# Power.net
KiCad netlist of a schematic drawn in Altium Designer
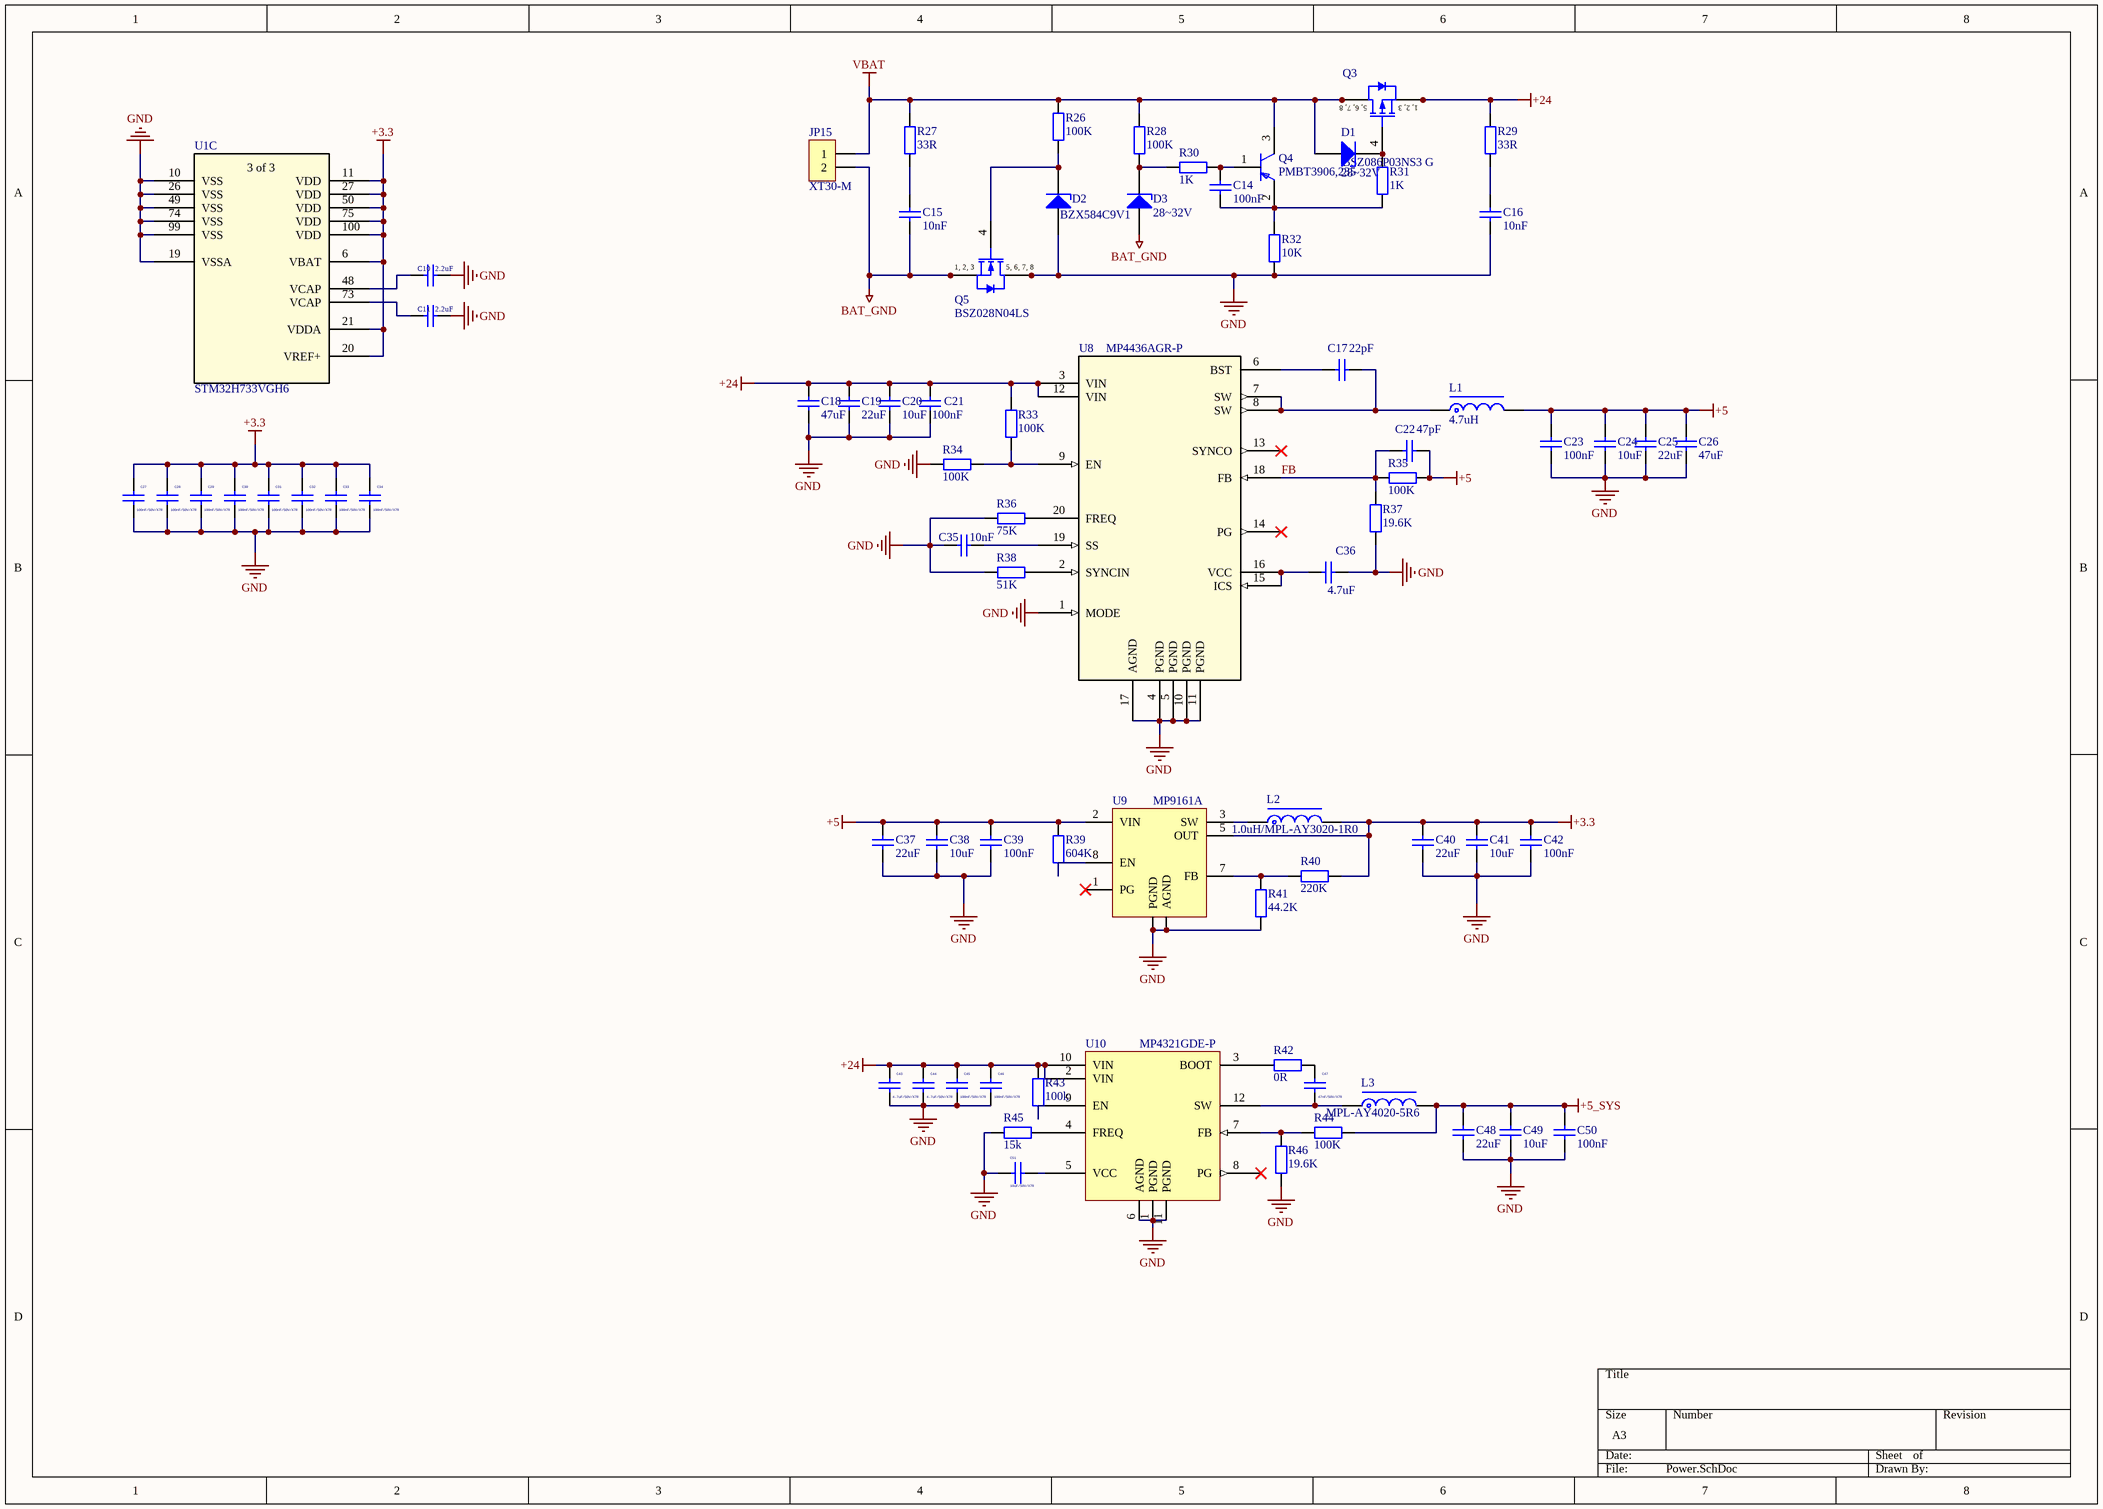
[diagram p0: Power.SchDoc]

(export (version "E")
  (design (tool "Eeschema 10.0.6"))
  (components
    (comp (ref "C10")
      (value "2.2uF")
      (footprint "C0402_L")
      (description "贴片电容/MLCC电容")
      (libsource (lib "0.1 - 电阻-电容-电感-保险丝-晶振-晶体-磁珠-电位器-法拉电容-馈通电容") (part "C"))
    )
    (comp (ref "C11")
      (value "2.2uF")
      (footprint "C0402_L")
      (description "贴片电容/MLCC电容")
      (libsource (lib "0.1 - 电阻-电容-电感-保险丝-晶振-晶体-磁珠-电位器-法拉电容-馈通电容") (part "C"))
    )
    (comp (ref "C14")
      (value "100nF")
      (footprint "C0402_M")
      (description "贴片电容/MLCC电容")
      (libsource (lib "海南大学MECHA战队") (part "C-EDLC"))
    )
    (comp (ref "C15")
      (value "10nF")
      (footprint "C0402_M")
      (description "贴片电容/MLCC电容")
      (libsource (lib "海南大学MECHA战队") (part "C-EDLC"))
    )
    (comp (ref "C16")
      (value "10nF")
      (footprint "C0402_M")
      (description "贴片电容/MLCC电容")
      (libsource (lib "海南大学MECHA战队") (part "C-EDLC"))
    )
    (comp (ref "C17")
      (value "22pF")
      (footprint "C0402_M")
      (description "贴片电容/MLCC电容")
      (libsource (lib "海南大学MECHA战队") (part "C-EDLC"))
    )
    (comp (ref "C18")
      (value "47uF")
      (footprint "C1206_L")
      (description "贴片电容/MLCC电容")
      (libsource (lib "0.1 - 电阻-电容-电感-保险丝-晶振-晶体-磁珠-电位器-法拉电容-馈通电容") (part "C"))
    )
    (comp (ref "C19")
      (value "22uF")
      (footprint "C0805_L")
      (description "贴片电容/MLCC电容")
      (libsource (lib "0.1 - 电阻-电容-电感-保险丝-晶振-晶体-磁珠-电位器-法拉电容-馈通电容") (part "C"))
    )
    (comp (ref "C20")
      (value "10uF")
      (footprint "C0603_L")
      (description "贴片电容/MLCC电容")
      (libsource (lib "0.1 - 电阻-电容-电感-保险丝-晶振-晶体-磁珠-电位器-法拉电容-馈通电容") (part "C"))
    )
    (comp (ref "C21")
      (value "100nF")
      (footprint "C0603_L")
      (description "贴片电容/MLCC电容")
      (libsource (lib "0.1 - 电阻-电容-电感-保险丝-晶振-晶体-磁珠-电位器-法拉电容-馈通电容") (part "C"))
    )
    (comp (ref "C22")
      (value "47pF")
      (footprint "C0402_M")
      (description "贴片电容/MLCC电容")
      (libsource (lib "海南大学MECHA战队") (part "C-EDLC"))
    )
    (comp (ref "C23")
      (value "100nF")
      (footprint "C0603_L")
      (description "贴片电容/MLCC电容")
      (libsource (lib "0.1 - 电阻-电容-电感-保险丝-晶振-晶体-磁珠-电位器-法拉电容-馈通电容") (part "C"))
    )
    (comp (ref "C24")
      (value "10uF")
      (footprint "C0603_L")
      (description "贴片电容/MLCC电容")
      (libsource (lib "0.1 - 电阻-电容-电感-保险丝-晶振-晶体-磁珠-电位器-法拉电容-馈通电容") (part "C"))
    )
    (comp (ref "C25")
      (value "22uF")
      (footprint "C0805_L")
      (description "贴片电容/MLCC电容")
      (libsource (lib "0.1 - 电阻-电容-电感-保险丝-晶振-晶体-磁珠-电位器-法拉电容-馈通电容") (part "C"))
    )
    (comp (ref "C26")
      (value "47uF")
      (footprint "C1206_L")
      (description "贴片电容/MLCC电容")
      (libsource (lib "0.1 - 电阻-电容-电感-保险丝-晶振-晶体-磁珠-电位器-法拉电容-馈通电容") (part "C"))
    )
    (comp (ref "C27")
      (value "100nF/50V/X7R")
      (footprint "C0402_L")
      (description "贴片电容/MLCC电容")
      (libsource (lib "0.1 - 电阻-电容-电感-保险丝-晶振-晶体-磁珠-电位器-法拉电容-馈通电容") (part "C"))
    )
    (comp (ref "C28")
      (value "100nF/50V/X7R")
      (footprint "C0402_L")
      (description "贴片电容/MLCC电容")
      (libsource (lib "0.1 - 电阻-电容-电感-保险丝-晶振-晶体-磁珠-电位器-法拉电容-馈通电容") (part "C"))
    )
    (comp (ref "C29")
      (value "100nF/50V/X7R")
      (footprint "C0402_L")
      (description "贴片电容/MLCC电容")
      (libsource (lib "0.1 - 电阻-电容-电感-保险丝-晶振-晶体-磁珠-电位器-法拉电容-馈通电容") (part "C"))
    )
    (comp (ref "C30")
      (value "100nF/50V/X7R")
      (footprint "C0402_L")
      (description "贴片电容/MLCC电容")
      (libsource (lib "0.1 - 电阻-电容-电感-保险丝-晶振-晶体-磁珠-电位器-法拉电容-馈通电容") (part "C"))
    )
    (comp (ref "C31")
      (value "100nF/50V/X7R")
      (footprint "C0402_L")
      (description "贴片电容/MLCC电容")
      (libsource (lib "0.1 - 电阻-电容-电感-保险丝-晶振-晶体-磁珠-电位器-法拉电容-馈通电容") (part "C"))
    )
    (comp (ref "C32")
      (value "100nF/50V/X7R")
      (footprint "C0402_L")
      (description "贴片电容/MLCC电容")
      (libsource (lib "0.1 - 电阻-电容-电感-保险丝-晶振-晶体-磁珠-电位器-法拉电容-馈通电容") (part "C"))
    )
    (comp (ref "C33")
      (value "100nF/50V/X7R")
      (footprint "C0402_L")
      (description "贴片电容/MLCC电容")
      (libsource (lib "0.1 - 电阻-电容-电感-保险丝-晶振-晶体-磁珠-电位器-法拉电容-馈通电容") (part "C"))
    )
    (comp (ref "C34")
      (value "100nF/50V/X7R")
      (footprint "C0402_L")
      (description "贴片电容/MLCC电容")
      (libsource (lib "0.1 - 电阻-电容-电感-保险丝-晶振-晶体-磁珠-电位器-法拉电容-馈通电容") (part "C"))
    )
    (comp (ref "C35")
      (value "10nF")
      (footprint "C0402_M")
      (description "贴片电容/MLCC电容")
      (libsource (lib "0.1 - 电阻-电容-电感-保险丝-晶振-晶体-磁珠-电位器-法拉电容-馈通电容") (part "C"))
    )
    (comp (ref "C36")
      (value "4.7uF")
      (footprint "C0402_M")
      (description "贴片电容/MLCC电容")
      (libsource (lib "0.1 - 电阻-电容-电感-保险丝-晶振-晶体-磁珠-电位器-法拉电容-馈通电容") (part "C"))
    )
    (comp (ref "C37")
      (value "22uF")
      (footprint "C0805_M")
      (description "贴片电容/MLCC电容")
      (libsource (lib "0.1 - 电阻-电容-电感-保险丝-晶振-晶体-磁珠-电位器-法拉电容-馈通电容") (part "C"))
    )
    (comp (ref "C38")
      (value "10uF")
      (footprint "C0603_M")
      (description "贴片电容/MLCC电容")
      (libsource (lib "0.1 - 电阻-电容-电感-保险丝-晶振-晶体-磁珠-电位器-法拉电容-馈通电容") (part "C"))
    )
    (comp (ref "C39")
      (value "100nF")
      (footprint "C0402_M")
      (description "贴片电容/MLCC电容")
      (libsource (lib "0.1 - 电阻-电容-电感-保险丝-晶振-晶体-磁珠-电位器-法拉电容-馈通电容") (part "C"))
    )
    (comp (ref "C40")
      (value "22uF")
      (footprint "C0603_M")
      (description "贴片电容/MLCC电容")
      (libsource (lib "0.1 - 电阻-电容-电感-保险丝-晶振-晶体-磁珠-电位器-法拉电容-馈通电容") (part "C"))
    )
    (comp (ref "C41")
      (value "10uF")
      (footprint "C0402_M")
      (description "贴片电容/MLCC电容")
      (libsource (lib "0.1 - 电阻-电容-电感-保险丝-晶振-晶体-磁珠-电位器-法拉电容-馈通电容") (part "C"))
    )
    (comp (ref "C42")
      (value "100nF")
      (footprint "C0402_M")
      (description "贴片电容/MLCC电容")
      (libsource (lib "0.1 - 电阻-电容-电感-保险丝-晶振-晶体-磁珠-电位器-法拉电容-馈通电容") (part "C"))
    )
    (comp (ref "C43")
      (value "4.7uF/50V/X7R")
      (footprint "C0402_L")
      (description "贴片电容/MLCC电容")
      (libsource (lib "0.1 - 电阻-电容-电感-保险丝-晶振-晶体-磁珠-电位器-法拉电容-馈通电容") (part "C"))
    )
    (comp (ref "C44")
      (value "4.7uF/50V/X7R")
      (footprint "C0402_L")
      (description "贴片电容/MLCC电容")
      (libsource (lib "0.1 - 电阻-电容-电感-保险丝-晶振-晶体-磁珠-电位器-法拉电容-馈通电容") (part "C"))
    )
    (comp (ref "C45")
      (value "100nF/50V/X7R")
      (footprint "C0402_L")
      (description "贴片电容/MLCC电容")
      (libsource (lib "0.1 - 电阻-电容-电感-保险丝-晶振-晶体-磁珠-电位器-法拉电容-馈通电容") (part "C"))
    )
    (comp (ref "C46")
      (value "100nF/50V/X7R")
      (footprint "C0402_L")
      (description "贴片电容/MLCC电容")
      (libsource (lib "0.1 - 电阻-电容-电感-保险丝-晶振-晶体-磁珠-电位器-法拉电容-馈通电容") (part "C"))
    )
    (comp (ref "C47")
      (value "47nF/50V/X7R")
      (footprint "C0402_L")
      (description "贴片电容/MLCC电容")
      (libsource (lib "0.1 - 电阻-电容-电感-保险丝-晶振-晶体-磁珠-电位器-法拉电容-馈通电容") (part "C"))
    )
    (comp (ref "C48")
      (value "22uF")
      (footprint "C0603_M")
      (description "贴片电容/MLCC电容")
      (libsource (lib "0.1 - 电阻-电容-电感-保险丝-晶振-晶体-磁珠-电位器-法拉电容-馈通电容") (part "C"))
    )
    (comp (ref "C49")
      (value "10uF")
      (footprint "C0402_M")
      (description "贴片电容/MLCC电容")
      (libsource (lib "0.1 - 电阻-电容-电感-保险丝-晶振-晶体-磁珠-电位器-法拉电容-馈通电容") (part "C"))
    )
    (comp (ref "C50")
      (value "100nF")
      (footprint "C0402_M")
      (description "贴片电容/MLCC电容")
      (libsource (lib "0.1 - 电阻-电容-电感-保险丝-晶振-晶体-磁珠-电位器-法拉电容-馈通电容") (part "C"))
    )
    (comp (ref "C51")
      (value "10uF/50V/X7R")
      (footprint "C0402_L")
      (description "贴片电容/MLCC电容")
      (libsource (lib "0.1 - 电阻-电容-电感-保险丝-晶振-晶体-磁珠-电位器-法拉电容-馈通电容") (part "C"))
    )
    (comp (ref "D1")
      (value "28~32V")
      (footprint "SOD-523")
      (description "Zener Diode")
      (libsource (lib "0.2 - 二极管-TVS-ESD-整流桥-放电管") (part "稳压二极管"))
    )
    (comp (ref "D2")
      (value "BZX584C9V1")
      (footprint "SOD-523")
      (description "Zener Diode")
      (libsource (lib "0.2 - 二极管-TVS-ESD-整流桥-放电管") (part "稳压二极管"))
    )
    (comp (ref "D3")
      (value "28~32V")
      (footprint "SOD-523")
      (description "Zener Diode")
      (libsource (lib "0.2 - 二极管-TVS-ESD-整流桥-放电管") (part "稳压二极管"))
    )
    (comp (ref "JP15")
      (value "XT30-M")
      (footprint "XT30PW-M")
      (description "XT30公头")
      (libsource (lib "0.6 - 电源_音频_USB Type-C_HDMI_XT60_5557_D-SUB_RJ45_SD-TF_SIM插座") (part "XT30-M"))
    )
    (comp (ref "L1")
      (value "4.7uH")
      (footprint "MPL-AL6050")
      (description "一体成型电感")
      (libsource (lib "0.1 - 电阻-电容-电感-保险丝-晶振-晶体-磁珠-电位器-法拉电容-馈通电容") (part "L-Molding Choke"))
    )
    (comp (ref "L2")
      (value "1.0uH/MPL-AY3020-1R0")
      (footprint "MPL-AY3020")
      (description "一体成型电感")
      (libsource (lib "0.1 - 电阻-电容-电感-保险丝-晶振-晶体-磁珠-电位器-法拉电容-馈通电容") (part "L-Molding Choke"))
    )
    (comp (ref "L3")
      (value "MPL-AY4020-5R6")
      (footprint "MPL-AY4020")
      (description "一体成型电感")
      (libsource (lib "0.1 - 电阻-电容-电感-保险丝-晶振-晶体-磁珠-电位器-法拉电容-馈通电容") (part "L-Molding Choke"))
    )
    (comp (ref "Q3")
      (value "BSZ086P03NS3 G")
      (footprint "INF-PG-TSDSON-8-1_V")
      (fields (field (name "MANUFACTURER") "Infineon"))
      (libsource (lib "Altium Content Vault") (part "INF-PEMOS-SSSGDDDD-8"))
    )
    (comp (ref "Q4")
      (value "PMBT3906,235")
      (footprint "FP-SOT23-IPC_C")
      (description "TRANS PNP 40V 200MA TO236AB")
      (libsource (lib "Altium Content Vault") (part "7fb3031473fedbfcc3b9251694f6eca"))
    )
    (comp (ref "Q5")
      (value "BSZ028N04LS")
      (footprint "INF-PG-TSDSON-8_FL_V")
      (description "N-Channel OptiMOS(TM) Power-MOSFET, 40 V VDS, 40 A ID, -55 to 150 degC, PG-TSDSON-8, Reel, Green")
      (fields (field (name "MANUFACTURER") "Infineon"))
      (libsource (lib "Altium Content Vault") (part "INF-NEMOS-SSSGDDDD-8"))
    )
    (comp (ref "R26")
      (value "100K")
      (footprint "R0402_M")
      (description "贴片电阻")
      (libsource (lib "海南大学MECHA战队") (part "R-High Precision"))
    )
    (comp (ref "R27")
      (value "33R")
      (footprint "R0402_M")
      (description "贴片电阻")
      (libsource (lib "海南大学MECHA战队") (part "R-High Precision"))
    )
    (comp (ref "R28")
      (value "100K")
      (footprint "R0402_M")
      (description "贴片电阻")
      (libsource (lib "海南大学MECHA战队") (part "R-High Precision"))
    )
    (comp (ref "R29")
      (value "33R")
      (footprint "R0402_M")
      (description "贴片电阻")
      (libsource (lib "海南大学MECHA战队") (part "R-High Precision"))
    )
    (comp (ref "R30")
      (value "1K")
      (footprint "R0402_M")
      (description "贴片电阻")
      (libsource (lib "海南大学MECHA战队") (part "R-High Precision"))
    )
    (comp (ref "R31")
      (value "1K")
      (footprint "R0402_M")
      (description "贴片电阻")
      (libsource (lib "海南大学MECHA战队") (part "R-High Precision"))
    )
    (comp (ref "R32")
      (value "10K")
      (footprint "R0402_M")
      (description "贴片电阻")
      (libsource (lib "海南大学MECHA战队") (part "R-High Precision"))
    )
    (comp (ref "R33")
      (value "100K")
      (footprint "R0402_M")
      (description "贴片电阻")
      (libsource (lib "海南大学MECHA战队") (part "R-High Precision"))
    )
    (comp (ref "R34")
      (value "100K")
      (footprint "R0402_M")
      (description "贴片电阻")
      (libsource (lib "海南大学MECHA战队") (part "R-High Precision"))
    )
    (comp (ref "R35")
      (value "100K")
      (footprint "R0402_M")
      (description "贴片电阻")
      (libsource (lib "海南大学MECHA战队") (part "R-High Precision"))
    )
    (comp (ref "R36")
      (value "75K")
      (footprint "R0402_M")
      (description "贴片电阻")
      (libsource (lib "海南大学MECHA战队") (part "R-High Precision"))
    )
    (comp (ref "R37")
      (value "19.6K")
      (footprint "R0402_M")
      (description "贴片电阻")
      (libsource (lib "海南大学MECHA战队") (part "R-High Precision"))
    )
    (comp (ref "R38")
      (value "51K")
      (footprint "R0402_M")
      (description "贴片电阻")
      (libsource (lib "海南大学MECHA战队") (part "R-High Precision"))
    )
    (comp (ref "R39")
      (value "604K")
      (footprint "R0402_L")
      (description "贴片电阻0")
      (libsource (lib "海南大学MECHA战队") (part "R-High Precision"))
    )
    (comp (ref "R40")
      (value "220K")
      (footprint "R0402_L")
      (description "贴片电阻0")
      (libsource (lib "海南大学MECHA战队") (part "R-High Precision"))
    )
    (comp (ref "R41")
      (value "44.2K")
      (footprint "R0402_L")
      (description "贴片电阻0")
      (libsource (lib "海南大学MECHA战队") (part "R-High Precision"))
    )
    (comp (ref "R42")
      (value "0R")
      (footprint "R0402_L")
      (description "贴片电阻0")
      (libsource (lib "海南大学MECHA战队") (part "R-High Precision"))
    )
    (comp (ref "R43")
      (value "100k")
      (footprint "R0402_L")
      (description "贴片电阻0")
      (libsource (lib "海南大学MECHA战队") (part "R-High Precision"))
    )
    (comp (ref "R44")
      (value "100K")
      (footprint "R0402_L")
      (description "贴片电阻0")
      (libsource (lib "海南大学MECHA战队") (part "R-High Precision"))
    )
    (comp (ref "R45")
      (value "15k")
      (footprint "R0402_L")
      (description "贴片电阻0")
      (libsource (lib "海南大学MECHA战队") (part "R-High Precision"))
    )
    (comp (ref "R46")
      (value "19.6K")
      (footprint "R0402_L")
      (description "贴片电阻0")
      (libsource (lib "海南大学MECHA战队") (part "R-High Precision"))
    )
    (comp (ref "U1")
      (value "STM32H733VGH6")
      (footprint "LQFP100_STM")
      (libsource (lib "HainanU-RoboMaster-硬件组") (part "STM32H733VGH6-Symbol-1"))
    )
    (comp (ref "U8")
      (value "MP4436AGR-P")
      (footprint "QFN-20_4MMX4MM_MPS")
      (description "QFN 20/ Synchronous Step-Down Converter 45V, 6A, Low Iq")
      (libsource (lib "海南大学MECHA战队") (part "MP4436AGR-P-Symbol-1"))
    )
    (comp (ref "U9") (value "MP9161A") (footprint "SOT23-8") (libsource (lib "海南大学MECHA战队") (part "MP9161A")))
    (comp (ref "U10")
      (value "MP4321GDE-P")
      (footprint "QFN-12_MP4321_MNP")
      (description "Voltage Regulator, DC/DC Gate Driver, 3.3 V to 36 V in, 0..8V to 34.2 V/1A Out, 2.42 MHz, QFN-12")
      (libsource (lib "HainanU-RoboMaster-硬件组") (part "MP4321GDE-P-Symbol-1"))
    )
  )
  (nets
    (net (code "1") (name "+3.3") (class "Default")
      (node (ref "C27") (pin "2") (pinfunction "2_2") (pintype "passive"))
      (node (ref "C28") (pin "2") (pinfunction "2_2") (pintype "passive"))
      (node (ref "C29") (pin "2") (pinfunction "2_2") (pintype "passive"))
      (node (ref "C30") (pin "2") (pinfunction "2_2") (pintype "passive"))
      (node (ref "C31") (pin "2") (pinfunction "2_2") (pintype "passive"))
      (node (ref "C32") (pin "2") (pinfunction "2_2") (pintype "passive"))
      (node (ref "C33") (pin "2") (pinfunction "2_2") (pintype "passive"))
      (node (ref "C34") (pin "2") (pinfunction "2_2") (pintype "passive"))
      (node (ref "C40") (pin "2") (pinfunction "2_2") (pintype "passive"))
      (node (ref "C41") (pin "2") (pinfunction "2_2") (pintype "passive"))
      (node (ref "C42") (pin "2") (pinfunction "2_2") (pintype "passive"))
      (node (ref "L2") (pin "2") (pinfunction "2_2") (pintype "passive"))
      (node (ref "R40") (pin "2") (pinfunction "2_2") (pintype "passive"))
      (node (ref "U1") (pin "100") (pinfunction "VDD_100") (pintype "power_in"))
      (node (ref "U1") (pin "11") (pinfunction "VDD_11") (pintype "power_in"))
      (node (ref "U1") (pin "20") (pinfunction "VREF+_20") (pintype "power_in"))
      (node (ref "U1") (pin "21") (pinfunction "VDDA_21") (pintype "power_in"))
      (node (ref "U1") (pin "27") (pinfunction "VDD_27") (pintype "power_in"))
      (node (ref "U1") (pin "50") (pinfunction "VDD_50") (pintype "power_in"))
      (node (ref "U1") (pin "6") (pinfunction "VBAT_6") (pintype "power_in"))
      (node (ref "U1") (pin "75") (pinfunction "VDD_75") (pintype "power_in"))
      (node (ref "U9") (pin "5") (pinfunction "OUT_5") (pintype "passive"))
    )
    (net (code "2") (name "+5") (class "Default")
      (node (ref "C22") (pin "2") (pinfunction "2_2") (pintype "passive"))
      (node (ref "C23") (pin "2") (pinfunction "2_2") (pintype "passive"))
      (node (ref "C24") (pin "2") (pinfunction "2_2") (pintype "passive"))
      (node (ref "C25") (pin "2") (pinfunction "2_2") (pintype "passive"))
      (node (ref "C26") (pin "1") (pinfunction "1_1") (pintype "passive"))
      (node (ref "C37") (pin "2") (pinfunction "2_2") (pintype "passive"))
      (node (ref "C38") (pin "2") (pinfunction "2_2") (pintype "passive"))
      (node (ref "C39") (pin "2") (pinfunction "2_2") (pintype "passive"))
      (node (ref "L1") (pin "2") (pinfunction "2_2") (pintype "passive"))
      (node (ref "R35") (pin "2") (pinfunction "2_2") (pintype "passive"))
      (node (ref "R39") (pin "2") (pinfunction "2_2") (pintype "passive"))
      (node (ref "U9") (pin "2") (pinfunction "VIN_2") (pintype "passive"))
    )
    (net (code "3") (name "+5_SYS") (class "Default")
      (node (ref "C48") (pin "2") (pinfunction "2_2") (pintype "passive"))
      (node (ref "C49") (pin "2") (pinfunction "2_2") (pintype "passive"))
      (node (ref "C50") (pin "2") (pinfunction "2_2") (pintype "passive"))
      (node (ref "L3") (pin "2") (pinfunction "2_2") (pintype "passive"))
      (node (ref "R44") (pin "1") (pinfunction "1_1") (pintype "passive"))
    )
    (net (code "4") (name "+24") (class "Default")
      (node (ref "C18") (pin "1") (pinfunction "1_1") (pintype "passive"))
      (node (ref "C19") (pin "1") (pinfunction "1_1") (pintype "passive"))
      (node (ref "C20") (pin "1") (pinfunction "1_1") (pintype "passive"))
      (node (ref "C21") (pin "1") (pinfunction "1_1") (pintype "passive"))
      (node (ref "C43") (pin "2") (pinfunction "2_2") (pintype "passive"))
      (node (ref "C44") (pin "2") (pinfunction "2_2") (pintype "passive"))
      (node (ref "C45") (pin "2") (pinfunction "2_2") (pintype "passive"))
      (node (ref "C46") (pin "2") (pinfunction "2_2") (pintype "passive"))
      (node (ref "Q3") (pin "1") (pinfunction "SOURCE_1") (pintype "passive"))
      (node (ref "Q3") (pin "2") (pinfunction "SOURCE_2") (pintype "passive"))
      (node (ref "Q3") (pin "3") (pinfunction "SOURCE_3") (pintype "passive"))
      (node (ref "R29") (pin "1") (pinfunction "1_1") (pintype "passive"))
      (node (ref "R33") (pin "2") (pinfunction "2_2") (pintype "passive"))
      (node (ref "R43") (pin "2") (pinfunction "2_2") (pintype "passive"))
      (node (ref "U10") (pin "10") (pinfunction "VIN_10") (pintype "power_in"))
      (node (ref "U10") (pin "2") (pinfunction "VIN_2") (pintype "power_in"))
      (node (ref "U8") (pin "12") (pinfunction "VIN_12") (pintype "power_in"))
      (node (ref "U8") (pin "3") (pinfunction "VIN_3") (pintype "power_in"))
    )
    (net (code "5") (name "/FB") (class "Default")
      (node (ref "C22") (pin "1") (pinfunction "1_1") (pintype "passive"))
      (node (ref "R35") (pin "1") (pinfunction "1_1") (pintype "passive"))
      (node (ref "R37") (pin "2") (pinfunction "2_2") (pintype "passive"))
      (node (ref "U8") (pin "18") (pinfunction "FB_18") (pintype "input"))
    )
    (net (code "6") (name "BAT_GND") (class "Default")
      (node (ref "C15") (pin "2") (pinfunction "2_2") (pintype "passive"))
      (node (ref "D3") (pin "1") (pinfunction "A_1") (pintype "passive"))
      (node (ref "JP15") (pin "2") (pinfunction "2_2") (pintype "passive"))
      (node (ref "Q5") (pin "1") (pinfunction "SOURCE_1") (pintype "passive"))
      (node (ref "Q5") (pin "2") (pinfunction "SOURCE_2") (pintype "passive"))
      (node (ref "Q5") (pin "3") (pinfunction "SOURCE_3") (pintype "passive"))
    )
    (net (code "7") (name "GND") (class "Default")
      (node (ref "C10") (pin "2") (pinfunction "2_2") (pintype "passive"))
      (node (ref "C11") (pin "2") (pinfunction "2_2") (pintype "passive"))
      (node (ref "C16") (pin "2") (pinfunction "2_2") (pintype "passive"))
      (node (ref "C18") (pin "2") (pinfunction "2_2") (pintype "passive"))
      (node (ref "C19") (pin "2") (pinfunction "2_2") (pintype "passive"))
      (node (ref "C20") (pin "2") (pinfunction "2_2") (pintype "passive"))
      (node (ref "C21") (pin "2") (pinfunction "2_2") (pintype "passive"))
      (node (ref "C23") (pin "1") (pinfunction "1_1") (pintype "passive"))
      (node (ref "C24") (pin "1") (pinfunction "1_1") (pintype "passive"))
      (node (ref "C25") (pin "1") (pinfunction "1_1") (pintype "passive"))
      (node (ref "C26") (pin "2") (pinfunction "2_2") (pintype "passive"))
      (node (ref "C27") (pin "1") (pinfunction "1_1") (pintype "passive"))
      (node (ref "C28") (pin "1") (pinfunction "1_1") (pintype "passive"))
      (node (ref "C29") (pin "1") (pinfunction "1_1") (pintype "passive"))
      (node (ref "C30") (pin "1") (pinfunction "1_1") (pintype "passive"))
      (node (ref "C31") (pin "1") (pinfunction "1_1") (pintype "passive"))
      (node (ref "C32") (pin "1") (pinfunction "1_1") (pintype "passive"))
      (node (ref "C33") (pin "1") (pinfunction "1_1") (pintype "passive"))
      (node (ref "C34") (pin "1") (pinfunction "1_1") (pintype "passive"))
      (node (ref "C35") (pin "1") (pinfunction "1_1") (pintype "passive"))
      (node (ref "C36") (pin "1") (pinfunction "1_1") (pintype "passive"))
      (node (ref "C37") (pin "1") (pinfunction "1_1") (pintype "passive"))
      (node (ref "C38") (pin "1") (pinfunction "1_1") (pintype "passive"))
      (node (ref "C39") (pin "1") (pinfunction "1_1") (pintype "passive"))
      (node (ref "C40") (pin "1") (pinfunction "1_1") (pintype "passive"))
      (node (ref "C41") (pin "1") (pinfunction "1_1") (pintype "passive"))
      (node (ref "C42") (pin "1") (pinfunction "1_1") (pintype "passive"))
      (node (ref "C43") (pin "1") (pinfunction "1_1") (pintype "passive"))
      (node (ref "C44") (pin "1") (pinfunction "1_1") (pintype "passive"))
      (node (ref "C45") (pin "1") (pinfunction "1_1") (pintype "passive"))
      (node (ref "C46") (pin "1") (pinfunction "1_1") (pintype "passive"))
      (node (ref "C48") (pin "1") (pinfunction "1_1") (pintype "passive"))
      (node (ref "C49") (pin "1") (pinfunction "1_1") (pintype "passive"))
      (node (ref "C50") (pin "1") (pinfunction "1_1") (pintype "passive"))
      (node (ref "C51") (pin "2") (pinfunction "2_2") (pintype "passive"))
      (node (ref "D2") (pin "1") (pinfunction "A_1") (pintype "passive"))
      (node (ref "Q5") (pin "5") (pinfunction "DRAIN_5") (pintype "passive"))
      (node (ref "Q5") (pin "6") (pinfunction "DRAIN_6") (pintype "passive"))
      (node (ref "Q5") (pin "7") (pinfunction "DRAIN_7") (pintype "passive"))
      (node (ref "Q5") (pin "8") (pinfunction "DRAIN_8") (pintype "passive"))
      (node (ref "R32") (pin "2") (pinfunction "2_2") (pintype "passive"))
      (node (ref "R34") (pin "2") (pinfunction "2_2") (pintype "passive"))
      (node (ref "R36") (pin "2") (pinfunction "2_2") (pintype "passive"))
      (node (ref "R37") (pin "1") (pinfunction "1_1") (pintype "passive"))
      (node (ref "R38") (pin "2") (pinfunction "2_2") (pintype "passive"))
      (node (ref "R41") (pin "2") (pinfunction "2_2") (pintype "passive"))
      (node (ref "R45") (pin "2") (pinfunction "2_2") (pintype "passive"))
      (node (ref "R46") (pin "2") (pinfunction "2_2") (pintype "passive"))
      (node (ref "U1") (pin "10") (pinfunction "VSS_10") (pintype "power_in"))
      (node (ref "U1") (pin "19") (pinfunction "VSSA_19") (pintype "power_in"))
      (node (ref "U1") (pin "26") (pinfunction "VSS_26") (pintype "power_in"))
      (node (ref "U1") (pin "49") (pinfunction "VSS_49") (pintype "power_in"))
      (node (ref "U1") (pin "74") (pinfunction "VSS_74") (pintype "power_in"))
      (node (ref "U1") (pin "99") (pinfunction "VSS_99") (pintype "power_in"))
      (node (ref "U10") (pin "1") (pinfunction "PGND_1") (pintype "power_in"))
      (node (ref "U10") (pin "11") (pinfunction "PGND_11") (pintype "power_in"))
      (node (ref "U10") (pin "6") (pinfunction "AGND_6") (pintype "power_in"))
      (node (ref "U8") (pin "1") (pinfunction "MODE_1") (pintype "input"))
      (node (ref "U8") (pin "10") (pinfunction "PGND_10") (pintype "power_in"))
      (node (ref "U8") (pin "11") (pinfunction "PGND_11") (pintype "power_in"))
      (node (ref "U8") (pin "17") (pinfunction "AGND_17") (pintype "power_in"))
      (node (ref "U8") (pin "4") (pinfunction "PGND_4") (pintype "power_in"))
      (node (ref "U8") (pin "5") (pinfunction "PGND_5") (pintype "power_in"))
      (node (ref "U9") (pin "4") (pinfunction "PGND_4") (pintype "passive"))
      (node (ref "U9") (pin "6") (pinfunction "AGND_6") (pintype "passive"))
    )
    (net (code "8") (name "Net-(C10-Pad1)") (class "Default")
      (node (ref "C10") (pin "1") (pinfunction "1_1") (pintype "passive"))
      (node (ref "U1") (pin "48") (pinfunction "VCAP_48") (pintype "power_in"))
    )
    (net (code "9") (name "Net-(C11-Pad1)") (class "Default")
      (node (ref "C11") (pin "1") (pinfunction "1_1") (pintype "passive"))
      (node (ref "U1") (pin "73") (pinfunction "VCAP_73") (pintype "power_in"))
    )
    (net (code "10") (name "Net-(C15-Pad1)") (class "Default")
      (node (ref "C15") (pin "1") (pinfunction "1_1") (pintype "passive"))
      (node (ref "R27") (pin "1") (pinfunction "1_1") (pintype "passive"))
    )
    (net (code "11") (name "Net-(C16-Pad1)") (class "Default")
      (node (ref "C16") (pin "1") (pinfunction "1_1") (pintype "passive"))
      (node (ref "R29") (pin "2") (pinfunction "2_2") (pintype "passive"))
    )
    (net (code "12") (name "Net-(C17-Pad2)") (class "Default")
      (node (ref "C17") (pin "2") (pinfunction "2_2") (pintype "passive"))
      (node (ref "L1") (pin "1") (pinfunction "1_1") (pintype "passive"))
      (node (ref "U8") (pin "7") (pinfunction "SW_7") (pintype "output"))
      (node (ref "U8") (pin "8") (pinfunction "SW_8") (pintype "output"))
    )
    (net (code "13") (name "Net-(C47-Pad2)") (class "Default")
      (node (ref "C47") (pin "2") (pinfunction "2_2") (pintype "passive"))
      (node (ref "R42") (pin "1") (pinfunction "1_1") (pintype "passive"))
    )
    (net (code "14") (name "Net-(D1-K)") (class "Default")
      (node (ref "D1") (pin "2") (pinfunction "K_2") (pintype "passive"))
      (node (ref "Q3") (pin "4") (pinfunction "GATE_4") (pintype "passive"))
      (node (ref "R31") (pin "1") (pinfunction "1_1") (pintype "passive"))
    )
    (net (code "15") (name "Net-(D2-K)") (class "Default")
      (node (ref "D2") (pin "2") (pinfunction "K_2") (pintype "passive"))
      (node (ref "Q5") (pin "4") (pinfunction "GATE_4") (pintype "passive"))
      (node (ref "R26") (pin "1") (pinfunction "1_1") (pintype "passive"))
    )
    (net (code "16") (name "Net-(D3-K)") (class "Default")
      (node (ref "D3") (pin "2") (pinfunction "K_2") (pintype "passive"))
      (node (ref "R28") (pin "1") (pinfunction "1_1") (pintype "passive"))
      (node (ref "R30") (pin "2") (pinfunction "2_2") (pintype "passive"))
    )
    (net (code "17") (name "Net-(Q4-B)") (class "Default")
      (node (ref "C14") (pin "1") (pinfunction "1_1") (pintype "passive"))
      (node (ref "Q4") (pin "1") (pinfunction "B_1") (pintype "passive"))
      (node (ref "R30") (pin "1") (pinfunction "1_1") (pintype "passive"))
    )
    (net (code "18") (name "Net-(Q4-E)") (class "Default")
      (node (ref "C14") (pin "2") (pinfunction "2_2") (pintype "passive"))
      (node (ref "Q4") (pin "2") (pinfunction "E_2") (pintype "passive"))
      (node (ref "R31") (pin "2") (pinfunction "2_2") (pintype "passive"))
      (node (ref "R32") (pin "1") (pinfunction "1_1") (pintype "passive"))
    )
    (net (code "19") (name "Net-(U8-BST)") (class "Default")
      (node (ref "C17") (pin "1") (pinfunction "1_1") (pintype "passive"))
      (node (ref "U8") (pin "6") (pinfunction "BST_6") (pintype "power_in"))
    )
    (net (code "20") (name "Net-(U8-EN)") (class "Default")
      (node (ref "R33") (pin "1") (pinfunction "1_1") (pintype "passive"))
      (node (ref "R34") (pin "1") (pinfunction "1_1") (pintype "passive"))
      (node (ref "U8") (pin "9") (pinfunction "EN_9") (pintype "input"))
    )
    (net (code "21") (name "Net-(U8-FREQ)") (class "Default")
      (node (ref "R36") (pin "1") (pinfunction "1_1") (pintype "passive"))
      (node (ref "U8") (pin "20") (pinfunction "FREQ_20") (pintype "passive"))
    )
    (net (code "22") (name "Net-(U8-ICS)") (class "Default")
      (node (ref "C36") (pin "2") (pinfunction "2_2") (pintype "passive"))
      (node (ref "U8") (pin "15") (pinfunction "ICS_15") (pintype "input"))
      (node (ref "U8") (pin "16") (pinfunction "VCC_16") (pintype "power_in"))
    )
    (net (code "23") (name "Net-(U8-SS)") (class "Default")
      (node (ref "C35") (pin "2") (pinfunction "2_2") (pintype "passive"))
      (node (ref "U8") (pin "19") (pinfunction "SS_19") (pintype "input"))
    )
    (net (code "24") (name "Net-(U8-SYNCIN)") (class "Default")
      (node (ref "R38") (pin "1") (pinfunction "1_1") (pintype "passive"))
      (node (ref "U8") (pin "2") (pinfunction "SYNCIN_2") (pintype "input"))
    )
    (net (code "25") (name "Net-(U9-EN)") (class "Default")
      (node (ref "R39") (pin "1") (pinfunction "1_1") (pintype "passive"))
      (node (ref "U9") (pin "8") (pinfunction "EN_8") (pintype "passive"))
    )
    (net (code "26") (name "Net-(U9-FB)") (class "Default")
      (node (ref "R40") (pin "1") (pinfunction "1_1") (pintype "passive"))
      (node (ref "R41") (pin "1") (pinfunction "1_1") (pintype "passive"))
      (node (ref "U9") (pin "7") (pinfunction "FB_7") (pintype "passive"))
    )
    (net (code "27") (name "Net-(U9-SW)") (class "Default")
      (node (ref "L2") (pin "1") (pinfunction "1_1") (pintype "passive"))
      (node (ref "U9") (pin "3") (pinfunction "SW_3") (pintype "passive"))
    )
    (net (code "28") (name "Net-(U10-BOOT)") (class "Default")
      (node (ref "R42") (pin "2") (pinfunction "2_2") (pintype "passive"))
      (node (ref "U10") (pin "3") (pinfunction "BOOT_3") (pintype "power_in"))
    )
    (net (code "29") (name "Net-(U10-EN)") (class "Default")
      (node (ref "R43") (pin "1") (pinfunction "1_1") (pintype "passive"))
      (node (ref "U10") (pin "9") (pinfunction "EN_9") (pintype "passive"))
    )
    (net (code "30") (name "Net-(U10-FB)") (class "Default")
      (node (ref "R44") (pin "2") (pinfunction "2_2") (pintype "passive"))
      (node (ref "R46") (pin "1") (pinfunction "1_1") (pintype "passive"))
      (node (ref "U10") (pin "7") (pinfunction "FB_7") (pintype "input"))
    )
    (net (code "31") (name "Net-(U10-FREQ)") (class "Default")
      (node (ref "R45") (pin "1") (pinfunction "1_1") (pintype "passive"))
      (node (ref "U10") (pin "4") (pinfunction "FREQ_4") (pintype "passive"))
    )
    (net (code "32") (name "Net-(U10-SW)") (class "Default")
      (node (ref "C47") (pin "1") (pinfunction "1_1") (pintype "passive"))
      (node (ref "L3") (pin "1") (pinfunction "1_1") (pintype "passive"))
      (node (ref "U10") (pin "12") (pinfunction "SW_12") (pintype "passive"))
    )
    (net (code "33") (name "Net-(U10-VCC)") (class "Default")
      (node (ref "C51") (pin "1") (pinfunction "1_1") (pintype "passive"))
      (node (ref "U10") (pin "5") (pinfunction "VCC_5") (pintype "power_in"))
    )
    (net (code "34") (name "VBAT") (class "Default")
      (node (ref "D1") (pin "1") (pinfunction "A_1") (pintype "passive"))
      (node (ref "JP15") (pin "1") (pinfunction "1_1") (pintype "passive"))
      (node (ref "Q3") (pin "5") (pinfunction "DRAIN_5") (pintype "passive"))
      (node (ref "Q3") (pin "6") (pinfunction "DRAIN_6") (pintype "passive"))
      (node (ref "Q3") (pin "7") (pinfunction "DRAIN_7") (pintype "passive"))
      (node (ref "Q3") (pin "8") (pinfunction "DRAIN_8") (pintype "passive"))
      (node (ref "Q4") (pin "3") (pinfunction "C_3") (pintype "passive"))
      (node (ref "R26") (pin "2") (pinfunction "2_2") (pintype "passive"))
      (node (ref "R27") (pin "2") (pinfunction "2_2") (pintype "passive"))
      (node (ref "R28") (pin "2") (pinfunction "2_2") (pintype "passive"))
    )
    (net (code "35") (name "unconnected-(U8-PG-Pad14)") (class "Default")
      (node (ref "U8") (pin "14") (pinfunction "PG_14") (pintype "output+no_connect"))
    )
    (net (code "36") (name "unconnected-(U8-SYNCO-Pad13)") (class "Default")
      (node (ref "U8") (pin "13") (pinfunction "SYNCO_13") (pintype "output+no_connect"))
    )
    (net (code "37") (name "unconnected-(U9-PG-Pad1)") (class "Default")
      (node (ref "U9") (pin "1") (pinfunction "PG_1") (pintype "passive+no_connect"))
    )
    (net (code "38") (name "unconnected-(U10-PG-Pad8)") (class "Default")
      (node (ref "U10") (pin "8") (pinfunction "PG_8") (pintype "output+no_connect"))
    )
  )
)
